# Medir-220-4.net
KiCad netlist of a schematic drawn in EAGLE
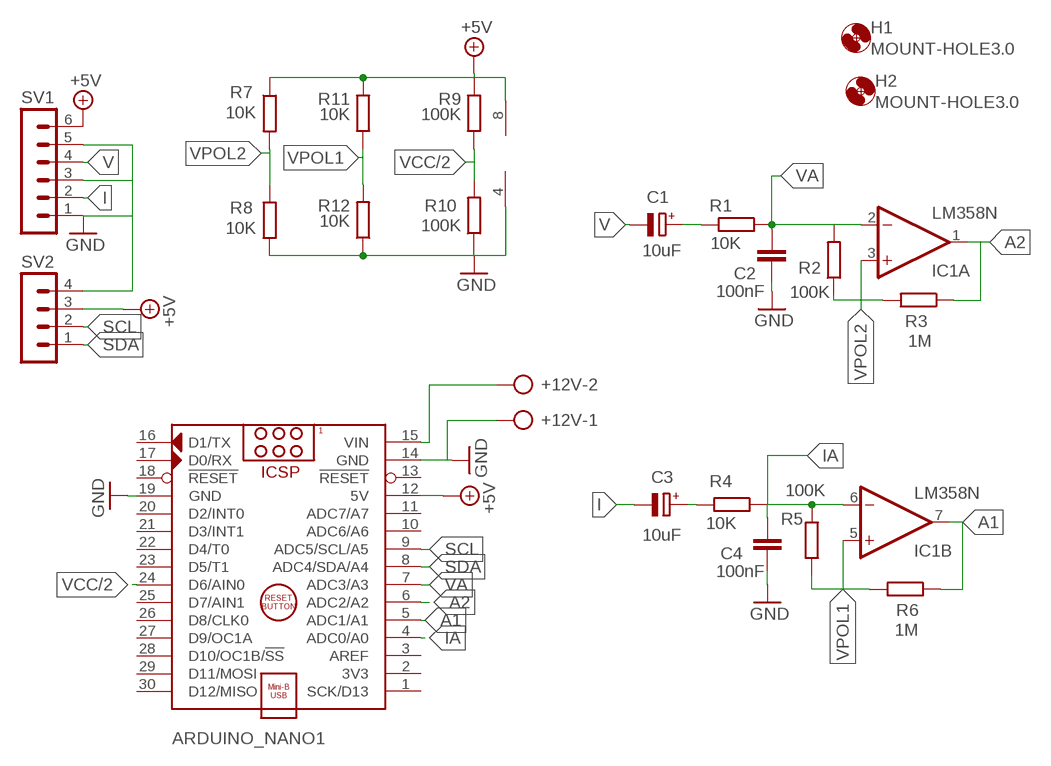
[diagram p0: schematic, sheet 1]

(export (version "E")
  (design (tool "Eeschema 10.0.6"))
  (components
    (comp (ref "+12V")
      (value "AK500/2")
      (footprint "eagle-import:AK500_2")
      (libsource (lib "eagle-import") (part "AK500/2"))
    )
    (comp (ref "ARDUINO_NANO1")
      (value "ARDUINO_NANO")
      (footprint "eagle-import:ARDUINO_NANO")
      (libsource (lib "eagle-import") (part "ARDUINO_NANO"))
    )
    (comp (ref "C1")
      (value "10uF")
      (footprint "eagle-import:E2,5-5")
      (libsource (lib "eagle-import") (part "CPOL-EUE2.5-5"))
    )
    (comp (ref "C2")
      (value "100nF")
      (footprint "eagle-import:C050-025X075")
      (libsource (lib "eagle-import") (part "C-EU050-025X075"))
    )
    (comp (ref "C3")
      (value "10uF")
      (footprint "eagle-import:E2,5-5")
      (libsource (lib "eagle-import") (part "CPOL-EUE2.5-5"))
    )
    (comp (ref "C4")
      (value "100nF")
      (footprint "eagle-import:C050-025X075")
      (libsource (lib "eagle-import") (part "C-EU050-025X075"))
    )
    (comp (ref "H1")
      (value "MOUNT-HOLE3.0")
      (footprint "eagle-import:3,0")
      (libsource (lib "eagle-import") (part "MOUNT-HOLE3.0"))
    )
    (comp (ref "H2")
      (value "MOUNT-HOLE3.0")
      (footprint "eagle-import:3,0")
      (libsource (lib "eagle-import") (part "MOUNT-HOLE3.0"))
    )
    (comp (ref "IC1")
      (value "LM358N")
      (footprint "eagle-import:DIL08")
      (libsource (lib "eagle-import") (part "LM358N"))
    )
    (comp (ref "R1")
      (value "10K")
      (footprint "eagle-import:0207_7")
      (libsource (lib "eagle-import") (part "resistor_R-EU_0207/7"))
    )
    (comp (ref "R2")
      (value "100K")
      (footprint "eagle-import:0207_7")
      (libsource (lib "eagle-import") (part "resistor_R-EU_0207/7"))
    )
    (comp (ref "R3")
      (value "1M")
      (footprint "eagle-import:0207_7")
      (libsource (lib "eagle-import") (part "resistor_R-EU_0207/7"))
    )
    (comp (ref "R4")
      (value "10K")
      (footprint "eagle-import:0207_7")
      (libsource (lib "eagle-import") (part "resistor_R-EU_0207/7"))
    )
    (comp (ref "R5")
      (value "100K")
      (footprint "eagle-import:0207_7")
      (libsource (lib "eagle-import") (part "resistor_R-EU_0207/7"))
    )
    (comp (ref "R6")
      (value "1M")
      (footprint "eagle-import:0207_7")
      (libsource (lib "eagle-import") (part "resistor_R-EU_0207/7"))
    )
    (comp (ref "R7")
      (value "10K")
      (footprint "eagle-import:0207_7")
      (libsource (lib "eagle-import") (part "resistor_R-EU_0207/7"))
    )
    (comp (ref "R8")
      (value "10K")
      (footprint "eagle-import:0207_7")
      (libsource (lib "eagle-import") (part "resistor_R-EU_0207/7"))
    )
    (comp (ref "R9")
      (value "100K")
      (footprint "eagle-import:0207_10")
      (libsource (lib "eagle-import") (part "R-EU_0207/10"))
    )
    (comp (ref "R10")
      (value "100K")
      (footprint "eagle-import:0207_10")
      (libsource (lib "eagle-import") (part "R-EU_0207/10"))
    )
    (comp (ref "R11")
      (value "10K")
      (footprint "eagle-import:0207_7")
      (libsource (lib "eagle-import") (part "resistor_R-EU_0207/7"))
    )
    (comp (ref "R12")
      (value "10K")
      (footprint "eagle-import:0207_7")
      (libsource (lib "eagle-import") (part "resistor_R-EU_0207/7"))
    )
    (comp (ref "SV1")
      (value "MA06-1")
      (footprint "eagle-import:MA06-1")
      (libsource (lib "eagle-import") (part "MA06-1"))
    )
    (comp (ref "SV2")
      (value "MA04-1")
      (footprint "eagle-import:MA04-1")
      (libsource (lib "eagle-import") (part "MA04-1"))
    )
  )
  (nets
    (net (code "1") (name "+5V") (class "Default")
      (node (ref "ARDUINO_NANO1") (pin "12") (pinfunction "5V_12") (pintype "power_in"))
      (node (ref "IC1") (pin "8") (pinfunction "V+_8") (pintype "power_in"))
      (node (ref "R11") (pin "2") (pinfunction "2_2") (pintype "passive"))
      (node (ref "R7") (pin "1") (pinfunction "1_1") (pintype "passive"))
      (node (ref "R9") (pin "2") (pinfunction "2_2") (pintype "passive"))
      (node (ref "SV1") (pin "6") (pinfunction "6_6") (pintype "passive"))
      (node (ref "SV2") (pin "3") (pinfunction "3_3") (pintype "passive"))
    )
    (net (code "2") (name "A1") (class "Default")
      (node (ref "ARDUINO_NANO1") (pin "5") (pinfunction "ADC1/A1_5") (pintype "bidirectional"))
      (node (ref "IC1") (pin "7") (pinfunction "OUT_7") (pintype "output"))
      (node (ref "R6") (pin "1") (pinfunction "1_1") (pintype "passive"))
    )
    (net (code "3") (name "A2") (class "Default")
      (node (ref "ARDUINO_NANO1") (pin "6") (pinfunction "ADC2/A2_6") (pintype "bidirectional"))
      (node (ref "IC1") (pin "1") (pinfunction "OUT_1") (pintype "output"))
      (node (ref "R3") (pin "1") (pinfunction "1_1") (pintype "passive"))
    )
    (net (code "4") (name "GND") (class "Default")
      (node (ref "+12V") (pin "1") (pinfunction "KL_1") (pintype "passive"))
      (node (ref "ARDUINO_NANO1") (pin "14") (pinfunction "GND_14") (pintype "power_in"))
      (node (ref "ARDUINO_NANO1") (pin "19") (pinfunction "GND_19") (pintype "power_in"))
      (node (ref "C2") (pin "2") (pinfunction "2_2") (pintype "passive"))
      (node (ref "C4") (pin "2") (pinfunction "2_2") (pintype "passive"))
      (node (ref "IC1") (pin "4") (pinfunction "V-_4") (pintype "power_in"))
      (node (ref "R10") (pin "1") (pinfunction "1_1") (pintype "passive"))
      (node (ref "R12") (pin "1") (pinfunction "1_1") (pintype "passive"))
      (node (ref "R8") (pin "2") (pinfunction "2_2") (pintype "passive"))
      (node (ref "SV1") (pin "1") (pinfunction "1_1") (pintype "passive"))
      (node (ref "SV1") (pin "3") (pinfunction "3_3") (pintype "passive"))
      (node (ref "SV1") (pin "5") (pinfunction "5_5") (pintype "passive"))
      (node (ref "SV2") (pin "4") (pinfunction "4_4") (pintype "passive"))
    )
    (net (code "5") (name "I") (class "Default")
      (node (ref "C3") (pin "-") (pinfunction "-_-") (pintype "passive"))
      (node (ref "SV1") (pin "2") (pinfunction "2_2") (pintype "passive"))
    )
    (net (code "6") (name "IA") (class "Default")
      (node (ref "ARDUINO_NANO1") (pin "4") (pinfunction "ADC0/A0_4") (pintype "bidirectional"))
      (node (ref "C4") (pin "1") (pinfunction "1_1") (pintype "passive"))
      (node (ref "IC1") (pin "6") (pinfunction "-IN_6") (pintype "input"))
      (node (ref "R4") (pin "1") (pinfunction "1_1") (pintype "passive"))
      (node (ref "R5") (pin "1") (pinfunction "1_1") (pintype "passive"))
    )
    (net (code "7") (name "Net-(+12VB-KL)") (class "Default")
      (node (ref "+12V") (pin "2") (pinfunction "KL_2") (pintype "passive"))
      (node (ref "ARDUINO_NANO1") (pin "15") (pinfunction "VIN_15") (pintype "power_in"))
    )
    (net (code "8") (name "Net-(C1-Pad+)") (class "Default")
      (node (ref "C1") (pin "+") (pinfunction "+_+") (pintype "passive"))
      (node (ref "R1") (pin "2") (pinfunction "2_2") (pintype "passive"))
    )
    (net (code "9") (name "Net-(C3-Pad+)") (class "Default")
      (node (ref "C3") (pin "+") (pinfunction "+_+") (pintype "passive"))
      (node (ref "R4") (pin "2") (pinfunction "2_2") (pintype "passive"))
    )
    (net (code "10") (name "SCL") (class "Default")
      (node (ref "ARDUINO_NANO1") (pin "9") (pinfunction "ADC5/SCL/A5_9") (pintype "bidirectional"))
      (node (ref "SV2") (pin "2") (pinfunction "2_2") (pintype "passive"))
    )
    (net (code "11") (name "SDA") (class "Default")
      (node (ref "ARDUINO_NANO1") (pin "8") (pinfunction "ADC4/SDA/A4_8") (pintype "bidirectional"))
      (node (ref "SV2") (pin "1") (pinfunction "1_1") (pintype "passive"))
    )
    (net (code "12") (name "V") (class "Default")
      (node (ref "C1") (pin "-") (pinfunction "-_-") (pintype "passive"))
      (node (ref "SV1") (pin "4") (pinfunction "4_4") (pintype "passive"))
    )
    (net (code "13") (name "VA") (class "Default")
      (node (ref "ARDUINO_NANO1") (pin "7") (pinfunction "ADC3/A3_7") (pintype "bidirectional"))
      (node (ref "C2") (pin "1") (pinfunction "1_1") (pintype "passive"))
      (node (ref "IC1") (pin "2") (pinfunction "-IN_2") (pintype "input"))
      (node (ref "R1") (pin "1") (pinfunction "1_1") (pintype "passive"))
      (node (ref "R2") (pin "2") (pinfunction "2_2") (pintype "passive"))
    )
    (net (code "14") (name "VCC{slash}2") (class "Default")
      (node (ref "ARDUINO_NANO1") (pin "24") (pinfunction "D6/AIN0_24") (pintype "bidirectional"))
      (node (ref "R10") (pin "2") (pinfunction "2_2") (pintype "passive"))
      (node (ref "R9") (pin "1") (pinfunction "1_1") (pintype "passive"))
    )
    (net (code "15") (name "VPOL1") (class "Default")
      (node (ref "IC1") (pin "5") (pinfunction "+IN_5") (pintype "input"))
      (node (ref "R11") (pin "1") (pinfunction "1_1") (pintype "passive"))
      (node (ref "R12") (pin "2") (pinfunction "2_2") (pintype "passive"))
      (node (ref "R5") (pin "2") (pinfunction "2_2") (pintype "passive"))
      (node (ref "R6") (pin "2") (pinfunction "2_2") (pintype "passive"))
    )
    (net (code "16") (name "VPOL2") (class "Default")
      (node (ref "IC1") (pin "3") (pinfunction "+IN_3") (pintype "input"))
      (node (ref "R2") (pin "1") (pinfunction "1_1") (pintype "passive"))
      (node (ref "R3") (pin "2") (pinfunction "2_2") (pintype "passive"))
      (node (ref "R7") (pin "2") (pinfunction "2_2") (pintype "passive"))
      (node (ref "R8") (pin "1") (pinfunction "1_1") (pintype "passive"))
    )
    (net (code "17") (name "unconnected-(ARDUINO_NANO1-3V3-Pad2)") (class "Default")
      (node (ref "ARDUINO_NANO1") (pin "2") (pinfunction "3V3_2") (pintype "output"))
    )
    (net (code "18") (name "unconnected-(ARDUINO_NANO1-ADC6{slash}A6-Pad10)") (class "Default")
      (node (ref "ARDUINO_NANO1") (pin "10") (pinfunction "ADC6/A6_10") (pintype "bidirectional"))
    )
    (net (code "19") (name "unconnected-(ARDUINO_NANO1-ADC7{slash}A7-Pad11)") (class "Default")
      (node (ref "ARDUINO_NANO1") (pin "11") (pinfunction "ADC7/A7_11") (pintype "bidirectional"))
    )
    (net (code "20") (name "unconnected-(ARDUINO_NANO1-AREF-Pad3)") (class "Default")
      (node (ref "ARDUINO_NANO1") (pin "3") (pinfunction "AREF_3") (pintype "input"))
    )
    (net (code "21") (name "unconnected-(ARDUINO_NANO1-D0{slash}RX-Pad17)") (class "Default")
      (node (ref "ARDUINO_NANO1") (pin "17") (pinfunction "D0/RX_17") (pintype "bidirectional"))
    )
    (net (code "22") (name "unconnected-(ARDUINO_NANO1-D1{slash}TX-Pad16)") (class "Default")
      (node (ref "ARDUINO_NANO1") (pin "16") (pinfunction "D1/TX_16") (pintype "bidirectional"))
    )
    (net (code "23") (name "unconnected-(ARDUINO_NANO1-D2{slash}INT0-Pad20)") (class "Default")
      (node (ref "ARDUINO_NANO1") (pin "20") (pinfunction "D2/INT0_20") (pintype "bidirectional"))
    )
    (net (code "24") (name "unconnected-(ARDUINO_NANO1-D3{slash}INT1-Pad21)") (class "Default")
      (node (ref "ARDUINO_NANO1") (pin "21") (pinfunction "D3/INT1_21") (pintype "bidirectional"))
    )
    (net (code "25") (name "unconnected-(ARDUINO_NANO1-D4{slash}T0-Pad22)") (class "Default")
      (node (ref "ARDUINO_NANO1") (pin "22") (pinfunction "D4/T0_22") (pintype "bidirectional"))
    )
    (net (code "26") (name "unconnected-(ARDUINO_NANO1-D5{slash}T1-Pad23)") (class "Default")
      (node (ref "ARDUINO_NANO1") (pin "23") (pinfunction "D5/T1_23") (pintype "bidirectional"))
    )
    (net (code "27") (name "unconnected-(ARDUINO_NANO1-D7{slash}AIN1-Pad25)") (class "Default")
      (node (ref "ARDUINO_NANO1") (pin "25") (pinfunction "D7/AIN1_25") (pintype "bidirectional"))
    )
    (net (code "28") (name "unconnected-(ARDUINO_NANO1-D8{slash}CLK0-Pad26)") (class "Default")
      (node (ref "ARDUINO_NANO1") (pin "26") (pinfunction "D8/CLK0_26") (pintype "bidirectional"))
    )
    (net (code "29") (name "unconnected-(ARDUINO_NANO1-D9{slash}OC1A-Pad27)") (class "Default")
      (node (ref "ARDUINO_NANO1") (pin "27") (pinfunction "D9/OC1A_27") (pintype "bidirectional"))
    )
    (net (code "30") (name "unconnected-(ARDUINO_NANO1-D10{slash}OC1B{slash}~{SS}-Pad28)") (class "Default")
      (node (ref "ARDUINO_NANO1") (pin "28") (pinfunction "D10/OC1B/~{SS}_28") (pintype "bidirectional"))
    )
    (net (code "31") (name "unconnected-(ARDUINO_NANO1-D11{slash}MOSI-Pad29)") (class "Default")
      (node (ref "ARDUINO_NANO1") (pin "29") (pinfunction "D11/MOSI_29") (pintype "bidirectional"))
    )
    (net (code "32") (name "unconnected-(ARDUINO_NANO1-D12{slash}MISO-Pad30)") (class "Default")
      (node (ref "ARDUINO_NANO1") (pin "30") (pinfunction "D12/MISO_30") (pintype "bidirectional"))
    )
    (net (code "33") (name "unconnected-(ARDUINO_NANO1-SCK{slash}D13-Pad1)") (class "Default")
      (node (ref "ARDUINO_NANO1") (pin "1") (pinfunction "SCK/D13_1") (pintype "bidirectional"))
    )
    (net (code "34") (name "unconnected-(ARDUINO_NANO1-~{RESET}-Pad13)") (class "Default")
      (node (ref "ARDUINO_NANO1") (pin "13") (pinfunction "~{RESET}_13") (pintype "input"))
    )
    (net (code "35") (name "unconnected-(ARDUINO_NANO1-~{RESET}-Pad18)") (class "Default")
      (node (ref "ARDUINO_NANO1") (pin "18") (pinfunction "~{RESET}_18") (pintype "input"))
    )
  )
)
